# POWER_GEN.net
KiCad netlist of a schematic drawn in Altium Designer
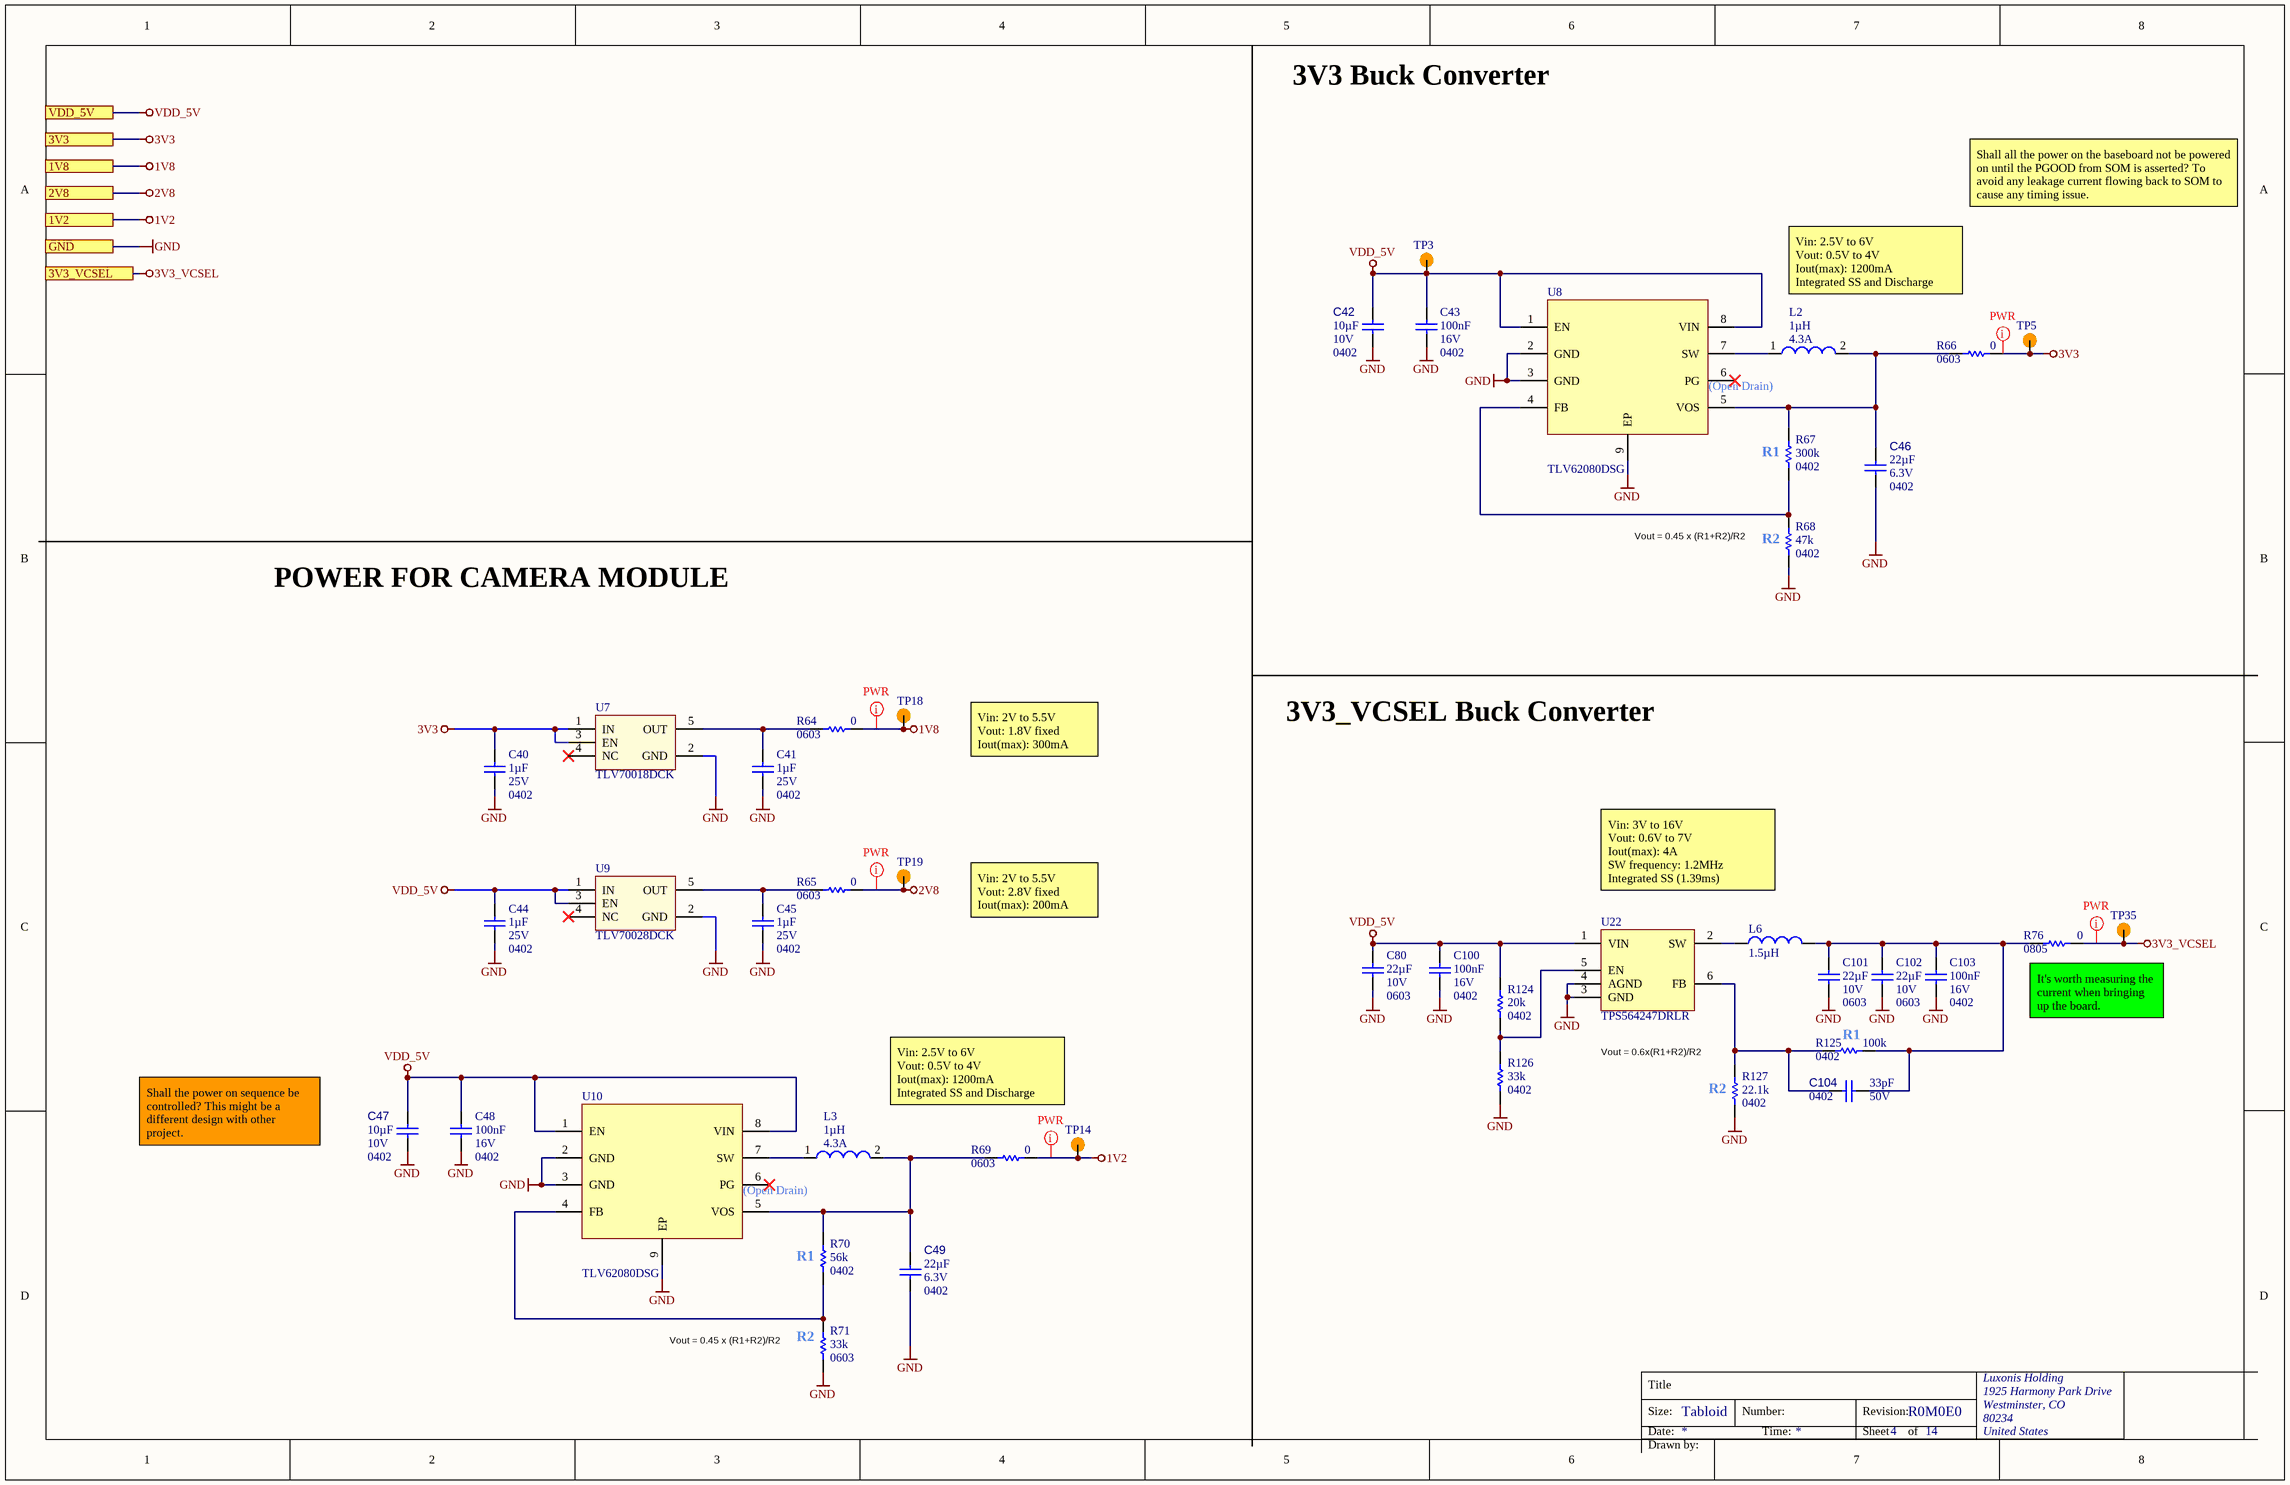
[diagram p0: POWER_GEN.SchDoc]

(export (version "E")
  (design (tool "Eeschema 10.0.6"))
  (components
    (comp (ref "C40")
      (value "1µF")
      (footprint "CAPC0402(1005)70_N")
      (description "CAP CER 1UF 25V X5R 0402 10%")
      (fields
        (field (name "VOLTAGE RATING") "25V")
        (field (name "CASE/PACKAGE") "0402")
        (field (name "TOLERANCE") "10%")
        (field (name "Comment") "GRM155R61E105KA12D")
      )
      (libsource (lib "Luxonis LLC") (part "GRM188R61C475KAAJD"))
    )
    (comp (ref "C41")
      (value "1µF")
      (footprint "CAPC0402(1005)70_N")
      (description "CAP CER 1UF 25V X5R 0402 10%")
      (fields
        (field (name "VOLTAGE RATING") "25V")
        (field (name "CASE/PACKAGE") "0402")
        (field (name "TOLERANCE") "10%")
        (field (name "Comment") "GRM155R61E105KA12D")
      )
      (libsource (lib "Luxonis LLC") (part "GRM188R61C475KAAJD"))
    )
    (comp (ref "C42")
      (value "10µF")
      (footprint "CAPC0402(1005)60_L")
      (description "CAP CER 10UF 10V X5R 0402 20%")
      (fields
        (field (name "VOLTAGE RATING") "10V")
        (field (name "TOLERANCE") "20%")
        (field (name "CASE/PACKAGE") "0402")
        (field (name "Comment") "GRM155R61A106ME11D")
      )
      (libsource (lib "Luxonis LLC") (part "*"))
    )
    (comp (ref "C43")
      (value "100nF")
      (footprint "CAPC0402(1005)60_N")
      (description "CAP CER 0.1UF 16V X7R 0402 10%")
      (fields
        (field (name "VOLTAGE RATING") "16V")
        (field (name "CASE/PACKAGE") "0402")
        (field (name "TOLERANCE") "10%")
        (field (name "Comment") "CL05B104KO5NFNC")
      )
      (libsource (lib "Luxonis LLC") (part "GRM188R61C475KAAJD"))
    )
    (comp (ref "C44")
      (value "1µF")
      (footprint "CAPC0402(1005)70_N")
      (description "CAP CER 1UF 25V X5R 0402 10%")
      (fields
        (field (name "VOLTAGE RATING") "25V")
        (field (name "CASE/PACKAGE") "0402")
        (field (name "TOLERANCE") "10%")
        (field (name "Comment") "GRM155R61E105KA12D")
      )
      (libsource (lib "Luxonis LLC") (part "GRM188R61C475KAAJD"))
    )
    (comp (ref "C45")
      (value "1µF")
      (footprint "CAPC0402(1005)70_N")
      (description "CAP CER 1UF 25V X5R 0402 10%")
      (fields
        (field (name "VOLTAGE RATING") "25V")
        (field (name "CASE/PACKAGE") "0402")
        (field (name "TOLERANCE") "10%")
        (field (name "Comment") "GRM155R61E105KA12D")
      )
      (libsource (lib "Luxonis LLC") (part "GRM188R61C475KAAJD"))
    )
    (comp (ref "C46")
      (value "22µF")
      (footprint "CAPC0402(1005)60_L")
      (description "CAP CER 22UF 6.3V X5R 0402 20%")
      (fields
        (field (name "VOLTAGE RATING") "6.3V")
        (field (name "CASE/PACKAGE") "0402")
        (field (name "TOLERANCE") "20%")
        (field (name "Comment") "CL05A226MQ5N6J8")
      )
      (libsource (lib "Luxonis LLC") (part "*"))
    )
    (comp (ref "C47")
      (value "10µF")
      (footprint "CAPC0402(1005)60_L")
      (description "CAP CER 10UF 10V X5R 0402 20%")
      (fields
        (field (name "VOLTAGE RATING") "10V")
        (field (name "TOLERANCE") "20%")
        (field (name "CASE/PACKAGE") "0402")
        (field (name "Comment") "GRM155R61A106ME11D")
      )
      (libsource (lib "Luxonis LLC") (part "*"))
    )
    (comp (ref "C48")
      (value "100nF")
      (footprint "CAPC0402(1005)60_N")
      (description "CAP CER 0.1UF 16V X7R 0402 10%")
      (fields
        (field (name "VOLTAGE RATING") "16V")
        (field (name "CASE/PACKAGE") "0402")
        (field (name "TOLERANCE") "10%")
        (field (name "Comment") "CL05B104KO5NFNC")
      )
      (libsource (lib "Luxonis LLC") (part "GRM188R61C475KAAJD"))
    )
    (comp (ref "C49")
      (value "22µF")
      (footprint "CAPC0402(1005)60_L")
      (description "CAP CER 22UF 6.3V X5R 0402 20%")
      (fields
        (field (name "VOLTAGE RATING") "6.3V")
        (field (name "CASE/PACKAGE") "0402")
        (field (name "TOLERANCE") "20%")
        (field (name "Comment") "CL05A226MQ5N6J8")
      )
      (libsource (lib "Luxonis LLC") (part "*"))
    )
    (comp (ref "C80")
      (value "22µF")
      (footprint "CAPC0603(1608)100_N")
      (description "CAP CER 22UF 10V X5R 0603 20%")
      (fields
        (field (name "VOLTAGE RATING") "10V")
        (field (name "CASE/PACKAGE") "0603")
        (field (name "TOLERANCE") "20%")
        (field (name "Comment") "GRM188R61A226ME15D")
      )
      (libsource (lib "Luxonis LLC") (part "GRM188R61C475KAAJD"))
    )
    (comp (ref "C100")
      (value "100nF")
      (footprint "CAPC0402(1005)60_N")
      (description "CAP CER 0.1UF 16V X7R 0402 10%")
      (fields
        (field (name "VOLTAGE RATING") "16V")
        (field (name "CASE/PACKAGE") "0402")
        (field (name "TOLERANCE") "10%")
        (field (name "Comment") "CL05B104KO5NFNC")
      )
      (libsource (lib "Luxonis LLC") (part "GRM188R61C475KAAJD"))
    )
    (comp (ref "C101")
      (value "22µF")
      (footprint "CAPC0603(1608)100_N")
      (description "CAP CER 22UF 10V X5R 0603 20%")
      (fields
        (field (name "VOLTAGE RATING") "10V")
        (field (name "CASE/PACKAGE") "0603")
        (field (name "TOLERANCE") "20%")
        (field (name "Comment") "GRM188R61A226ME15D")
      )
      (libsource (lib "Luxonis LLC") (part "GRM188R61C475KAAJD"))
    )
    (comp (ref "C102")
      (value "22µF")
      (footprint "CAPC0603(1608)100_N")
      (description "CAP CER 22UF 10V X5R 0603 20%")
      (fields
        (field (name "VOLTAGE RATING") "10V")
        (field (name "CASE/PACKAGE") "0603")
        (field (name "TOLERANCE") "20%")
        (field (name "Comment") "GRM188R61A226ME15D")
      )
      (libsource (lib "Luxonis LLC") (part "GRM188R61C475KAAJD"))
    )
    (comp (ref "C103")
      (value "100nF")
      (footprint "CAPC0402(1005)60_N")
      (description "CAP CER 0.1UF 16V X7R 0402 10%")
      (fields
        (field (name "VOLTAGE RATING") "16V")
        (field (name "CASE/PACKAGE") "0402")
        (field (name "TOLERANCE") "10%")
        (field (name "Comment") "CL05B104KO5NFNC")
      )
      (libsource (lib "Luxonis LLC") (part "GRM188R61C475KAAJD"))
    )
    (comp (ref "C104")
      (value "33pF")
      (footprint "FP-GCM155-0_05-IPC_A")
      (description "CAP CER 33pF 50V C0G 0402 5%")
      (fields
        (field (name "VOLTAGE RATING") "50V")
        (field (name "CASE/PACKAGE") "0402")
        (field (name "TOLERANCE") "5%")
        (field (name "Comment") "GCM1555C1H330JA16D")
      )
      (libsource (lib "Luxonis LLC") (part "*"))
    )
    (comp (ref "L2")
      (value "1µH")
      (footprint "DFE252012P-1R0M=P2")
      (description "FIXED IND 1UH 3.2A 42 MOHM SMD")
      (fields
        (field (name "MANUFACTURER") "Murata")
        (field (name "MANUFACTURER PART NUMBER") "DFE252012P-1R0M=P2")
        (field (name "CURRENT RATING") "4.3A")
      )
      (libsource (lib "Luxonis LLC") (part "DFE252012P-1R0M=P2"))
    )
    (comp (ref "L3")
      (value "1µH")
      (footprint "DFE252012P-1R0M=P2")
      (description "FIXED IND 1UH 3.2A 42 MOHM SMD")
      (fields
        (field (name "MANUFACTURER") "Murata")
        (field (name "MANUFACTURER PART NUMBER") "DFE252012P-1R0M=P2")
        (field (name "CURRENT RATING") "4.3A")
      )
      (libsource (lib "Luxonis LLC") (part "DFE252012P-1R0M=P2"))
    )
    (comp (ref "L6")
      (value "1.5µH")
      (footprint "FP-SRP6540-MFG")
      (description "General Purpose Inductor, 1.5uH, 20%, 1 Element, Powdered Iron-Core, SMD, 2826")
      (fields (field (name "TOLERANCE") "20%") (field (name "Comment") "SRP6540-1R5M"))
      (libsource (lib "Luxonis LLC") (part "IND-2"))
    )
    (comp (ref "R64")
      (value "0")
      (footprint "RESC0603(1608)_N")
      (description "RES SMD 0 OHM 5% 1/10W 0603")
      (fields
        (field (name "TOLERANCE") "5%")
        (field (name "CASE/PACKAGE") "0603")
        (field (name "Comment") "CRCW06030000Z0EA")
      )
      (libsource (lib "Luxonis LLC") (part "RC0402FR-0722RL_1"))
    )
    (comp (ref "R65")
      (value "0")
      (footprint "RESC0603(1608)_N")
      (description "RES SMD 0 OHM 5% 1/10W 0603")
      (fields
        (field (name "TOLERANCE") "5%")
        (field (name "CASE/PACKAGE") "0603")
        (field (name "Comment") "CRCW06030000Z0EA")
      )
      (libsource (lib "Luxonis LLC") (part "RC0402FR-0722RL_1"))
    )
    (comp (ref "R66")
      (value "0")
      (footprint "RESC0603(1608)_N")
      (description "RES SMD 0 OHM 5% 1/10W 0603")
      (fields
        (field (name "TOLERANCE") "5%")
        (field (name "CASE/PACKAGE") "0603")
        (field (name "Comment") "CRCW06030000Z0EA")
      )
      (libsource (lib "Luxonis LLC") (part "RC0402FR-0722RL_1"))
    )
    (comp (ref "R67")
      (value "300k")
      (footprint "RESC0402(1005)_N")
      (description "RES SMD 300K OHM 1% 1/16W 0402")
      (fields
        (field (name "CASE/PACKAGE") "0402")
        (field (name "TOLERANCE") "1%")
        (field (name "Comment") "RC0402FR-07300KL")
      )
      (libsource (lib "Luxonis LLC") (part "Default resistor symbol"))
    )
    (comp (ref "R68")
      (value "47k")
      (footprint "RESC0402(1005)_L")
      (description "RES SMD 47K OHM 1% 1/16W 0402")
      (fields
        (field (name "CASE/PACKAGE") "0402")
        (field (name "TOLERANCE") "1%")
        (field (name "Comment") "RC0402FR-0747KL")
      )
      (libsource (lib "Luxonis LLC") (part "Default resistor symbol"))
    )
    (comp (ref "R69")
      (value "0")
      (footprint "RESC0603(1608)_N")
      (description "RES SMD 0 OHM 5% 1/10W 0603")
      (fields
        (field (name "TOLERANCE") "5%")
        (field (name "CASE/PACKAGE") "0603")
        (field (name "Comment") "CRCW06030000Z0EA")
      )
      (libsource (lib "Luxonis LLC") (part "RC0402FR-0722RL_1"))
    )
    (comp (ref "R70")
      (value "56k")
      (footprint "RESC0402(1005)_L")
      (description "RES SMD 56K OHM 1% 1/16W 0402")
      (fields
        (field (name "CASE/PACKAGE") "0402")
        (field (name "TOLERANCE") "1%")
        (field (name "Comment") "RC0402FR-0756KL")
      )
      (libsource (lib "Luxonis LLC") (part "Default resistor symbol"))
    )
    (comp (ref "R71")
      (value "33k")
      (footprint "RESC1608X55X25LL10T15")
      (description "RES SMD 33K OHM 1% 0.1W 0603")
      (fields
        (field (name "CASE/PACKAGE") "0603")
        (field (name "TOLERANCE") "1%")
        (field (name "Comment") "RC0603FR-0733KL")
      )
      (libsource (lib "Luxonis LLC") (part "Default resistor symbol"))
    )
    (comp (ref "R76")
      (value "0")
      (footprint "RESC0805(2012)_L")
      (description "RES SMD 0 OHM 1% 1/8W 0805")
      (fields (field (name "CASE/PACKAGE") "0805") (field (name "Comment") "CRCW08050000Z0EA"))
      (libsource (lib "Luxonis LLC") (part "Default resistor symbol"))
    )
    (comp (ref "R124")
      (value "20k")
      (footprint "RESC0402(1005)_L")
      (description "RES SMD 20K OHM 1% 1/16W 0402")
      (fields
        (field (name "CASE/PACKAGE") "0402")
        (field (name "TOLERANCE") "1%")
        (field (name "Comment") "RC0402FR-0720KL")
      )
      (libsource (lib "Luxonis LLC") (part "Default resistor symbol"))
    )
    (comp (ref "R125")
      (value "100k")
      (footprint "RESC0402(1005)_L")
      (description "RES SMD 100K OHM 1% 1/16W 0402")
      (fields
        (field (name "CASE/PACKAGE") "0402")
        (field (name "TOLERANCE") "1%")
        (field (name "Comment") "RC0402FR-07100KL")
      )
      (libsource (lib "Luxonis LLC") (part "Default resistor symbol"))
    )
    (comp (ref "R126")
      (value "33k")
      (footprint "RESC0402(1005)_L")
      (description "RES SMD 33K OHM 1% 1/16W 0402")
      (fields
        (field (name "CASE/PACKAGE") "0402")
        (field (name "TOLERANCE") "1%")
        (field (name "Comment") "CRCW040233K0FKED")
      )
      (libsource (lib "Luxonis LLC") (part "Default resistor symbol"))
    )
    (comp (ref "R127")
      (value "22.1k")
      (footprint "RESC0402(1005)_N")
      (description "RES SMD 22.1K OHM 1% 1/16W 0402")
      (fields
        (field (name "CASE/PACKAGE") "0402")
        (field (name "TOLERANCE") "1%")
        (field (name "Comment") "RC0402FR-0722K1L")
      )
      (libsource (lib "Luxonis LLC") (part "Default resistor symbol"))
    )
    (comp (ref "TP3")
      (value "TP075_150_NS")
      (footprint "LuxonisMaster:TP075_150_NS")
      (libsource (lib "LuxonisMaster") (part "TEST_POINT"))
    )
    (comp (ref "TP5")
      (value "TP075_150_NS")
      (footprint "LuxonisMaster:TP075_150_NS")
      (libsource (lib "LuxonisMaster") (part "TEST_POINT"))
    )
    (comp (ref "TP14")
      (value "TP075_150_NS")
      (footprint "LuxonisMaster:TP075_150_NS")
      (libsource (lib "LuxonisMaster") (part "TEST_POINT"))
    )
    (comp (ref "TP18")
      (value "TP075_150_NS")
      (footprint "LuxonisMaster:TP075_150_NS")
      (libsource (lib "LuxonisMaster") (part "TEST_POINT"))
    )
    (comp (ref "TP19")
      (value "TP075_150_NS")
      (footprint "LuxonisMaster:TP075_150_NS")
      (libsource (lib "LuxonisMaster") (part "TEST_POINT"))
    )
    (comp (ref "TP35")
      (value "TP075_150_NS")
      (footprint "LuxonisMaster:TP075_150_NS")
      (libsource (lib "LuxonisMaster") (part "TEST_POINT"))
    )
    (comp (ref "U7")
      (value "TLV70018DCK")
      (footprint "TLV70018DCK")
      (description "IC REG LINEAR 1.8V 200MA SC70-5 Linear Voltage Regulator IC  1 Output  200mA SC-70-5")
      (libsource (lib "Luxonis LLC") (part "TLV70018DCK"))
    )
    (comp (ref "U8")
      (value "TLV62080DSG")
      (footprint "TLV62080DSG")
      (description "IC REG BUCK ADJ 1.2A SYNC 8WSON")
      (libsource (lib "Luxonis LLC") (part "TLV62080DSG"))
    )
    (comp (ref "U9")
      (value "TLV70028DCK")
      (footprint "TLV70028DCK")
      (description "IC REG LINEAR 2.8V 200MA SC70-5 Linear Voltage Regulator IC  1 Output  200mA SC-70-5")
      (libsource (lib "Luxonis LLC") (part "TLV70028DCK"))
    )
    (comp (ref "U10")
      (value "TLV62080DSG")
      (footprint "TLV62080DSG")
      (description "IC REG BUCK ADJ 1.2A SYNC 8WSON")
      (libsource (lib "Luxonis LLC") (part "TLV62080DSG"))
    )
    (comp (ref "U22")
      (value "TPS564247DRLR")
      (footprint "TPS564247DRLR-Footprint-1")
      (libsource (lib "Luxonis LLC") (part "TPS564247DRLR-Symbol-1"))
    )
  )
  (nets
    (net (code "1") (name "1V2") (class "Default")
      (node (ref "R69") (pin "2") (pinfunction "2_2") (pintype "passive"))
      (node (ref "TP14") (pin "1") (pintype "passive"))
    )
    (net (code "2") (name "1V8") (class "Default")
      (node (ref "R64") (pin "2") (pinfunction "2_2") (pintype "passive"))
      (node (ref "TP18") (pin "1") (pintype "passive"))
    )
    (net (code "3") (name "2V8") (class "Default")
      (node (ref "R65") (pin "2") (pinfunction "2_2") (pintype "passive"))
      (node (ref "TP19") (pin "1") (pintype "passive"))
    )
    (net (code "4") (name "3V3") (class "Default")
      (node (ref "C40") (pin "2") (pinfunction "2_2") (pintype "passive"))
      (node (ref "R66") (pin "2") (pinfunction "2_2") (pintype "passive"))
      (node (ref "TP5") (pin "1") (pintype "passive"))
      (node (ref "U7") (pin "1") (pinfunction "IN_1") (pintype "passive"))
      (node (ref "U7") (pin "3") (pinfunction "EN_3") (pintype "passive"))
    )
    (net (code "5") (name "3V3_VCSEL") (class "Default")
      (node (ref "R76") (pin "2") (pinfunction "2_2") (pintype "passive"))
      (node (ref "TP35") (pin "1") (pintype "passive"))
    )
    (net (code "6") (name "GND") (class "Default")
      (node (ref "C100") (pin "1") (pinfunction "1_1") (pintype "passive"))
      (node (ref "C101") (pin "1") (pinfunction "1_1") (pintype "passive"))
      (node (ref "C102") (pin "1") (pinfunction "1_1") (pintype "passive"))
      (node (ref "C103") (pin "1") (pinfunction "1_1") (pintype "passive"))
      (node (ref "C40") (pin "1") (pinfunction "1_1") (pintype "passive"))
      (node (ref "C41") (pin "1") (pinfunction "1_1") (pintype "passive"))
      (node (ref "C42") (pin "1") (pinfunction "1_1") (pintype "passive"))
      (node (ref "C43") (pin "1") (pinfunction "1_1") (pintype "passive"))
      (node (ref "C44") (pin "1") (pinfunction "1_1") (pintype "passive"))
      (node (ref "C45") (pin "1") (pinfunction "1_1") (pintype "passive"))
      (node (ref "C46") (pin "1") (pinfunction "1_1") (pintype "passive"))
      (node (ref "C47") (pin "1") (pinfunction "1_1") (pintype "passive"))
      (node (ref "C48") (pin "1") (pinfunction "1_1") (pintype "passive"))
      (node (ref "C49") (pin "1") (pinfunction "1_1") (pintype "passive"))
      (node (ref "C80") (pin "1") (pinfunction "1_1") (pintype "passive"))
      (node (ref "R126") (pin "1") (pinfunction "1_1") (pintype "passive"))
      (node (ref "R127") (pin "1") (pinfunction "1_1") (pintype "passive"))
      (node (ref "R68") (pin "1") (pinfunction "1_1") (pintype "passive"))
      (node (ref "R71") (pin "1") (pinfunction "1_1") (pintype "passive"))
      (node (ref "U10") (pin "2") (pinfunction "GND_2") (pintype "passive"))
      (node (ref "U10") (pin "3") (pinfunction "GND_3") (pintype "passive"))
      (node (ref "U10") (pin "9") (pinfunction "EP_9") (pintype "passive"))
      (node (ref "U22") (pin "3") (pinfunction "GND_3") (pintype "passive"))
      (node (ref "U22") (pin "4") (pinfunction "AGND_4") (pintype "passive"))
      (node (ref "U7") (pin "2") (pinfunction "GND_2") (pintype "passive"))
      (node (ref "U8") (pin "2") (pinfunction "GND_2") (pintype "passive"))
      (node (ref "U8") (pin "3") (pinfunction "GND_3") (pintype "passive"))
      (node (ref "U8") (pin "9") (pinfunction "EP_9") (pintype "passive"))
      (node (ref "U9") (pin "2") (pinfunction "GND_2") (pintype "passive"))
    )
    (net (code "7") (name "Net-(C101-Pad2)") (class "Default")
      (node (ref "C101") (pin "2") (pinfunction "2_2") (pintype "passive"))
      (node (ref "C102") (pin "2") (pinfunction "2_2") (pintype "passive"))
      (node (ref "C103") (pin "2") (pinfunction "2_2") (pintype "passive"))
      (node (ref "C104") (pin "1") (pinfunction "1_1") (pintype "passive"))
      (node (ref "L6") (pin "2") (pinfunction "2_2") (pintype "passive"))
      (node (ref "R125") (pin "1") (pinfunction "1_1") (pintype "passive"))
      (node (ref "R76") (pin "1") (pinfunction "1_1") (pintype "passive"))
    )
    (net (code "8") (name "Net-(U7-OUT)") (class "Default")
      (node (ref "C41") (pin "2") (pinfunction "2_2") (pintype "passive"))
      (node (ref "R64") (pin "1") (pinfunction "1_1") (pintype "passive"))
      (node (ref "U7") (pin "5") (pinfunction "OUT_5") (pintype "passive"))
    )
    (net (code "9") (name "Net-(U8-FB)") (class "Default")
      (node (ref "R67") (pin "1") (pinfunction "1_1") (pintype "passive"))
      (node (ref "R68") (pin "2") (pinfunction "2_2") (pintype "passive"))
      (node (ref "U8") (pin "4") (pinfunction "FB_4") (pintype "passive"))
    )
    (net (code "10") (name "Net-(U8-SW)") (class "Default")
      (node (ref "L2") (pin "1") (pinfunction "1_1") (pintype "passive"))
      (node (ref "U8") (pin "7") (pinfunction "SW_7") (pintype "passive"))
    )
    (net (code "11") (name "Net-(U8-VOS)") (class "Default")
      (node (ref "C46") (pin "2") (pinfunction "2_2") (pintype "passive"))
      (node (ref "L2") (pin "2") (pinfunction "2_2") (pintype "passive"))
      (node (ref "R66") (pin "1") (pinfunction "1_1") (pintype "passive"))
      (node (ref "R67") (pin "2") (pinfunction "2_2") (pintype "passive"))
      (node (ref "U8") (pin "5") (pinfunction "VOS_5") (pintype "passive"))
    )
    (net (code "12") (name "Net-(U9-OUT)") (class "Default")
      (node (ref "C45") (pin "2") (pinfunction "2_2") (pintype "passive"))
      (node (ref "R65") (pin "1") (pinfunction "1_1") (pintype "passive"))
      (node (ref "U9") (pin "5") (pinfunction "OUT_5") (pintype "passive"))
    )
    (net (code "13") (name "Net-(U10-FB)") (class "Default")
      (node (ref "R70") (pin "1") (pinfunction "1_1") (pintype "passive"))
      (node (ref "R71") (pin "2") (pinfunction "2_2") (pintype "passive"))
      (node (ref "U10") (pin "4") (pinfunction "FB_4") (pintype "passive"))
    )
    (net (code "14") (name "Net-(U10-SW)") (class "Default")
      (node (ref "L3") (pin "1") (pinfunction "1_1") (pintype "passive"))
      (node (ref "U10") (pin "7") (pinfunction "SW_7") (pintype "passive"))
    )
    (net (code "15") (name "Net-(U10-VOS)") (class "Default")
      (node (ref "C49") (pin "2") (pinfunction "2_2") (pintype "passive"))
      (node (ref "L3") (pin "2") (pinfunction "2_2") (pintype "passive"))
      (node (ref "R69") (pin "1") (pinfunction "1_1") (pintype "passive"))
      (node (ref "R70") (pin "2") (pinfunction "2_2") (pintype "passive"))
      (node (ref "U10") (pin "5") (pinfunction "VOS_5") (pintype "passive"))
    )
    (net (code "16") (name "Net-(U22-EN)") (class "Default")
      (node (ref "R124") (pin "1") (pinfunction "1_1") (pintype "passive"))
      (node (ref "R126") (pin "2") (pinfunction "2_2") (pintype "passive"))
      (node (ref "U22") (pin "5") (pinfunction "EN_5") (pintype "passive"))
    )
    (net (code "17") (name "Net-(U22-FB)") (class "Default")
      (node (ref "C104") (pin "2") (pinfunction "2_2") (pintype "passive"))
      (node (ref "R125") (pin "2") (pinfunction "2_2") (pintype "passive"))
      (node (ref "R127") (pin "2") (pinfunction "2_2") (pintype "passive"))
      (node (ref "U22") (pin "6") (pinfunction "FB_6") (pintype "passive"))
    )
    (net (code "18") (name "Net-(U22-SW)") (class "Default")
      (node (ref "L6") (pin "1") (pinfunction "1_1") (pintype "passive"))
      (node (ref "U22") (pin "2") (pinfunction "SW_2") (pintype "passive"))
    )
    (net (code "19") (name "VDD_5V") (class "Default")
      (node (ref "C100") (pin "2") (pinfunction "2_2") (pintype "passive"))
      (node (ref "C42") (pin "2") (pinfunction "2_2") (pintype "passive"))
      (node (ref "C43") (pin "2") (pinfunction "2_2") (pintype "passive"))
      (node (ref "C44") (pin "2") (pinfunction "2_2") (pintype "passive"))
      (node (ref "C47") (pin "2") (pinfunction "2_2") (pintype "passive"))
      (node (ref "C48") (pin "2") (pinfunction "2_2") (pintype "passive"))
      (node (ref "C80") (pin "2") (pinfunction "2_2") (pintype "passive"))
      (node (ref "R124") (pin "2") (pinfunction "2_2") (pintype "passive"))
      (node (ref "TP3") (pin "1") (pintype "passive"))
      (node (ref "U10") (pin "1") (pinfunction "EN_1") (pintype "passive"))
      (node (ref "U10") (pin "8") (pinfunction "VIN_8") (pintype "passive"))
      (node (ref "U22") (pin "1") (pinfunction "VIN_1") (pintype "passive"))
      (node (ref "U8") (pin "1") (pinfunction "EN_1") (pintype "passive"))
      (node (ref "U8") (pin "8") (pinfunction "VIN_8") (pintype "passive"))
      (node (ref "U9") (pin "1") (pinfunction "IN_1") (pintype "passive"))
      (node (ref "U9") (pin "3") (pinfunction "EN_3") (pintype "passive"))
    )
    (net (code "20") (name "unconnected-(U7-NC-Pad4)") (class "Default")
      (node (ref "U7") (pin "4") (pinfunction "NC_4") (pintype "passive+no_connect"))
    )
    (net (code "21") (name "unconnected-(U8-PG-Pad6)") (class "Default")
      (node (ref "U8") (pin "6") (pinfunction "PG_6") (pintype "passive+no_connect"))
    )
    (net (code "22") (name "unconnected-(U9-NC-Pad4)") (class "Default")
      (node (ref "U9") (pin "4") (pinfunction "NC_4") (pintype "passive+no_connect"))
    )
    (net (code "23") (name "unconnected-(U10-PG-Pad6)") (class "Default")
      (node (ref "U10") (pin "6") (pinfunction "PG_6") (pintype "passive+no_connect"))
    )
  )
)
